# CSC4863.net
KiCad netlist of a schematic drawn in EAGLE
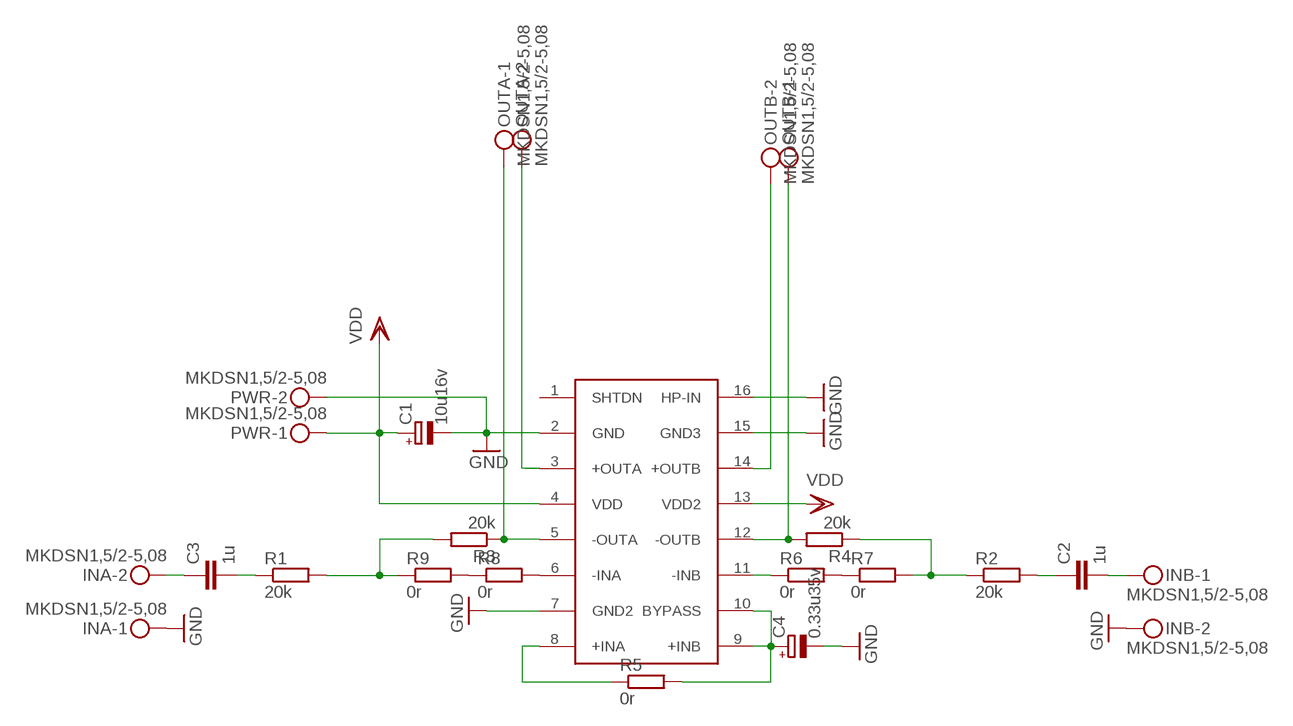
[diagram p0: schematic, sheet 1]

(export (version "E")
  (design (tool "Eeschema 10.0.6"))
  (components
    (comp (ref "C1")
      (value "10u16v")
      (footprint "eagle-import:SMC_A")
      (libsource (lib "eagle-import") (part "CPOL-EUSMCA"))
    )
    (comp (ref "C2")
      (value "1u")
      (footprint "eagle-import:C1206")
      (libsource (lib "eagle-import") (part "C-EUC1206"))
    )
    (comp (ref "C3")
      (value "1u")
      (footprint "eagle-import:C1206")
      (libsource (lib "eagle-import") (part "C-EUC1206"))
    )
    (comp (ref "C4")
      (value "0.33u35v")
      (footprint "eagle-import:SMC_A")
      (libsource (lib "eagle-import") (part "CPOL-EUSMCA"))
    )
    (comp (ref "INA")
      (value "MKDSN1,5/2-5,08")
      (footprint "eagle-import:MKDSN1,5_2-5,08")
      (libsource (lib "eagle-import") (part "MKDSN1,5/2-5,08"))
    )
    (comp (ref "INB")
      (value "MKDSN1,5/2-5,08")
      (footprint "eagle-import:MKDSN1,5_2-5,08")
      (libsource (lib "eagle-import") (part "MKDSN1,5/2-5,08"))
    )
    (comp (ref "OUTA")
      (value "MKDSN1,5/2-5,08")
      (footprint "eagle-import:MKDSN1,5_2-5,08")
      (libsource (lib "eagle-import") (part "MKDSN1,5/2-5,08"))
    )
    (comp (ref "OUTB")
      (value "MKDSN1,5/2-5,08")
      (footprint "eagle-import:MKDSN1,5_2-5,08")
      (libsource (lib "eagle-import") (part "MKDSN1,5/2-5,08"))
    )
    (comp (ref "PWR")
      (value "MKDSN1,5/2-5,08")
      (footprint "eagle-import:MKDSN1,5_2-5,08")
      (libsource (lib "eagle-import") (part "MKDSN1,5/2-5,08"))
    )
    (comp (ref "R1")
      (value "20k")
      (footprint "eagle-import:R1206")
      (libsource (lib "eagle-import") (part "R-EU_R1206"))
    )
    (comp (ref "R2")
      (value "20k")
      (footprint "eagle-import:R1206")
      (libsource (lib "eagle-import") (part "R-EU_R1206"))
    )
    (comp (ref "R3")
      (value "20k")
      (footprint "eagle-import:R1206")
      (libsource (lib "eagle-import") (part "R-EU_R1206"))
    )
    (comp (ref "R4")
      (value "20k")
      (footprint "eagle-import:R1206")
      (libsource (lib "eagle-import") (part "R-EU_R1206"))
    )
    (comp (ref "R5")
      (value "0r")
      (footprint "eagle-import:R1206")
      (libsource (lib "eagle-import") (part "R-EU_R1206"))
    )
    (comp (ref "R6")
      (value "0r")
      (footprint "eagle-import:R1206")
      (libsource (lib "eagle-import") (part "R-EU_R1206"))
    )
    (comp (ref "R7")
      (value "0r")
      (footprint "eagle-import:R1206")
      (libsource (lib "eagle-import") (part "R-EU_R1206"))
    )
    (comp (ref "R8")
      (value "0r")
      (footprint "eagle-import:R1206")
      (libsource (lib "eagle-import") (part "R-EU_R1206"))
    )
    (comp (ref "R9")
      (value "0r")
      (footprint "eagle-import:R1206")
      (libsource (lib "eagle-import") (part "R-EU_R1206"))
    )
    (comp (ref "U$1")
      (value "CSC4863")
      (footprint "eagle-import:SO16")
      (libsource (lib "eagle-import") (part "CSC4863"))
    )
  )
  (nets
    (net (code "1") (name "GND") (class "Default")
      (node (ref "C1") (pin "-") (pinfunction "-_-") (pintype "passive"))
      (node (ref "C4") (pin "-") (pinfunction "-_-") (pintype "passive"))
      (node (ref "INA") (pin "1") (pinfunction "KL_1") (pintype "passive"))
      (node (ref "INB") (pin "2") (pinfunction "KL_2") (pintype "passive"))
      (node (ref "PWR") (pin "2") (pinfunction "KL_2") (pintype "passive"))
      (node (ref "U$1") (pin "15") (pinfunction "GND3_15") (pintype "bidirectional"))
      (node (ref "U$1") (pin "16") (pinfunction "HP-IN_16") (pintype "bidirectional"))
      (node (ref "U$1") (pin "2") (pinfunction "GND_2") (pintype "bidirectional"))
      (node (ref "U$1") (pin "7") (pinfunction "GND2_7") (pintype "bidirectional"))
    )
    (net (code "2") (name "Net-(C2-Pad1)") (class "Default")
      (node (ref "C2") (pin "1") (pinfunction "1_1") (pintype "passive"))
      (node (ref "R2") (pin "2") (pinfunction "2_2") (pintype "passive"))
    )
    (net (code "3") (name "Net-(C3-Pad2)") (class "Default")
      (node (ref "C3") (pin "2") (pinfunction "2_2") (pintype "passive"))
      (node (ref "R1") (pin "1") (pinfunction "1_1") (pintype "passive"))
    )
    (net (code "4") (name "Net-(INAB-KL)") (class "Default")
      (node (ref "C3") (pin "1") (pinfunction "1_1") (pintype "passive"))
      (node (ref "INA") (pin "2") (pinfunction "KL_2") (pintype "passive"))
    )
    (net (code "5") (name "Net-(INBA-KL)") (class "Default")
      (node (ref "C2") (pin "2") (pinfunction "2_2") (pintype "passive"))
      (node (ref "INB") (pin "1") (pinfunction "KL_1") (pintype "passive"))
    )
    (net (code "6") (name "Net-(OUTAA-KL)") (class "Default")
      (node (ref "OUTA") (pin "1") (pinfunction "KL_1") (pintype "passive"))
      (node (ref "R3") (pin "1") (pinfunction "1_1") (pintype "passive"))
      (node (ref "U$1") (pin "5") (pinfunction "-OUTA_5") (pintype "bidirectional"))
    )
    (net (code "7") (name "Net-(OUTAB-KL)") (class "Default")
      (node (ref "OUTA") (pin "2") (pinfunction "KL_2") (pintype "passive"))
      (node (ref "U$1") (pin "3") (pinfunction "+OUTA_3") (pintype "bidirectional"))
    )
    (net (code "8") (name "Net-(OUTBA-KL)") (class "Default")
      (node (ref "OUTB") (pin "1") (pinfunction "KL_1") (pintype "passive"))
      (node (ref "R4") (pin "2") (pinfunction "2_2") (pintype "passive"))
      (node (ref "U$1") (pin "12") (pinfunction "-OUTB_12") (pintype "bidirectional"))
    )
    (net (code "9") (name "Net-(OUTBB-KL)") (class "Default")
      (node (ref "OUTB") (pin "2") (pinfunction "KL_2") (pintype "passive"))
      (node (ref "U$1") (pin "14") (pinfunction "+OUTB_14") (pintype "bidirectional"))
    )
    (net (code "10") (name "Net-(R1-Pad2)") (class "Default")
      (node (ref "R1") (pin "2") (pinfunction "2_2") (pintype "passive"))
      (node (ref "R3") (pin "2") (pinfunction "2_2") (pintype "passive"))
      (node (ref "R9") (pin "1") (pinfunction "1_1") (pintype "passive"))
    )
    (net (code "11") (name "Net-(R2-Pad1)") (class "Default")
      (node (ref "R2") (pin "1") (pinfunction "1_1") (pintype "passive"))
      (node (ref "R4") (pin "1") (pinfunction "1_1") (pintype "passive"))
      (node (ref "R7") (pin "2") (pinfunction "2_2") (pintype "passive"))
    )
    (net (code "12") (name "Net-(R6-Pad2)") (class "Default")
      (node (ref "R6") (pin "2") (pinfunction "2_2") (pintype "passive"))
      (node (ref "R7") (pin "1") (pinfunction "1_1") (pintype "passive"))
    )
    (net (code "13") (name "Net-(R8-Pad1)") (class "Default")
      (node (ref "R8") (pin "1") (pinfunction "1_1") (pintype "passive"))
      (node (ref "R9") (pin "2") (pinfunction "2_2") (pintype "passive"))
    )
    (net (code "14") (name "Net-(U$1-+INA)") (class "Default")
      (node (ref "R5") (pin "1") (pinfunction "1_1") (pintype "passive"))
      (node (ref "U$1") (pin "8") (pinfunction "+INA_8") (pintype "bidirectional"))
    )
    (net (code "15") (name "Net-(U$1-+INB)") (class "Default")
      (node (ref "C4") (pin "+") (pinfunction "+_+") (pintype "passive"))
      (node (ref "R5") (pin "2") (pinfunction "2_2") (pintype "passive"))
      (node (ref "U$1") (pin "10") (pinfunction "BYPASS_10") (pintype "bidirectional"))
      (node (ref "U$1") (pin "9") (pinfunction "+INB_9") (pintype "bidirectional"))
    )
    (net (code "16") (name "Net-(U$1--INA)") (class "Default")
      (node (ref "R8") (pin "2") (pinfunction "2_2") (pintype "passive"))
      (node (ref "U$1") (pin "6") (pinfunction "-INA_6") (pintype "bidirectional"))
    )
    (net (code "17") (name "Net-(U$1--INB)") (class "Default")
      (node (ref "R6") (pin "1") (pinfunction "1_1") (pintype "passive"))
      (node (ref "U$1") (pin "11") (pinfunction "-INB_11") (pintype "bidirectional"))
    )
    (net (code "18") (name "VDD") (class "Default")
      (node (ref "C1") (pin "+") (pinfunction "+_+") (pintype "passive"))
      (node (ref "PWR") (pin "1") (pinfunction "KL_1") (pintype "passive"))
      (node (ref "U$1") (pin "13") (pinfunction "VDD2_13") (pintype "bidirectional"))
      (node (ref "U$1") (pin "4") (pinfunction "VDD_4") (pintype "bidirectional"))
    )
    (net (code "19") (name "unconnected-(U$1-SHTDN-Pad1)") (class "Default")
      (node (ref "U$1") (pin "1") (pinfunction "SHTDN_1") (pintype "bidirectional"))
    )
  )
)
